# DIB_Power_Plane.net
KiCad netlist of a schematic drawn in Altium Designer
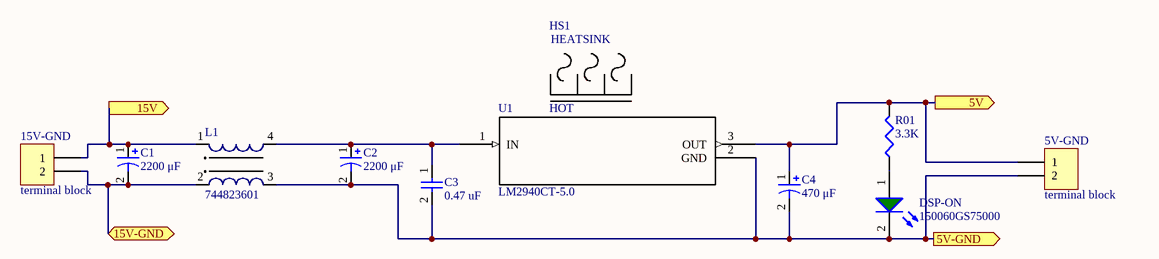
[diagram p0: DIB_Power_Plane.SchDoc]

(export (version "E")
  (design (tool "Eeschema 10.0.6"))
  (components
    (comp (ref "5V-GND")
      (value "terminal block")
      (footprint "691101710002")
      (description "WR-TBL Terminal block - serie 101-5.0mm")
      (fields
        (field (name "MANUFACTURER") "Würth Elektronik eiSos GmbH")
        (field (name "PARTNO") "691101710002")
        (field (name "CREATED BY") "Karrer Zheng")
      )
      (libsource (lib "Altium_TBL_5_00_101_HORIZONTAL_ENTRY_MODULAR_69110171000X_rev15e") (part "691101710002"))
    )
    (comp (ref "15V-GND")
      (value "terminal block")
      (footprint "691101710002")
      (description "WR-TBL Terminal block - serie 101-5.0mm")
      (fields
        (field (name "MANUFACTURER") "Würth Elektronik eiSos GmbH")
        (field (name "PARTNO") "691101710002")
        (field (name "CREATED BY") "Karrer Zheng")
      )
      (libsource (lib "") (part "691101710002_1"))
    )
    (comp (ref "C1")
      (value "2200 μF")
      (footprint "WCAP-ATG5 16x35.5x7.5x0.8")
      (description "WCAP-ATG5 Aluminum Electrolytic Capacitors , 2200 μF; + / - 20%; 50 V , 16 x 35,5")
      (fields
        (field (name "MANUFACTURER") "Wurth Elektronik")
        (field (name "PARTNO") "860020680030")
        (field (name "E-MAIL") "libraries@we-online.com")
        (field (name "CREATED BY") "Karrer Zheng")
      )
      (libsource (lib "WCAP-ATG5_rev15a") (part "WCAP-ATG5 16x35.5x7.5x0.8 860020680030"))
    )
    (comp (ref "C2")
      (value "2200 μF")
      (footprint "WCAP-ATG5 16x35.5x7.5x0.8")
      (description "WCAP-ATG5 Aluminum Electrolytic Capacitors , 2200 μF; + / - 20%; 50 V , 16 x 35,5")
      (fields
        (field (name "MANUFACTURER") "Wurth Elektronik")
        (field (name "PARTNO") "860020680030")
        (field (name "E-MAIL") "libraries@we-online.com")
        (field (name "CREATED BY") "Karrer Zheng")
      )
      (libsource (lib "WCAP-ATG5_rev15a") (part "WCAP-ATG5 16x35.5x7.5x0.8 860020680030"))
    )
    (comp (ref "C3")
      (value "0.47 uF")
      (footprint "WCAP-FTXX 7,5x10x12x6")
      (description "WCAP-FTXX Film Capacitors, C=68000 pF")
      (fields
        (field (name "MANUFACTURER") "Wurth Elektronik")
        (field (name "PARTNO") "890334022017")
        (field (name "E-MAIL") "libraries@we-online.com")
        (field (name "CREATED BY") "Karrer Zheng")
      )
      (libsource (lib "WCAP-FTXX_rev15a") (part "WCAP-FTXX 7,5x10x12x6 890334022017"))
    )
    (comp (ref "C4")
      (value "470 μF")
      (footprint "WCAP-ATG8 8x11.5x3.5x0.5")
      (description "WCAP-ATG8 Aluminum Electrolytic Capacitors , 470 μF; + / - 20%; 25 V , 8 x 11,5")
      (fields
        (field (name "MANUFACTURER") "Wurth Elektronik")
        (field (name "PARTNO") "860010474013")
        (field (name "E-MAIL") "libraries@we-online.com")
        (field (name "CREATED BY") "Karrer Zheng")
      )
      (libsource (lib "WCAP-ATG8_rev15a") (part "WCAP-ATG8 8x11.5x3.5x0.5 860010474013"))
    )
    (comp (ref "DSP-ON")
      (value "150060GS75000")
      (footprint "LED_0603_Green")
      (description "SMD mono-color Chip LED, WL-SMCW, Green")
      (fields
        (field (name "MANUFACTURER") "W黵th Elektronik eiSos GmbH")
        (field (name "CREATED BY") "Christin Otto")
      )
      (libsource (lib "WL-SMCW_rev15b") (part "WL-SMCW 0603  150060GS75000"))
    )
    (comp (ref "HS1")
      (value "HOT")
      (footprint "AAVID53002B02500G-custom")
      (description "TO 220 heat sink L=25mm; B=15mm; H= 30mm")
      (libsource (lib "sink block") (part "TO-220 Heat Sink"))
    )
    (comp (ref "L1")
      (value "744823601")
      (footprint "WE-CMB_M_744823601")
      (description "WE-CMB Common Mode Power Line Choke, L = 1.0mH")
      (fields (field (name "MANUFACTURER") "Wurth Elektronik") (field (name "CREATED BY") "Baojun Chen"))
      (libsource (lib "Altium_WE-CMB_rev16a") (part "WE-CMB M, 744823601"))
    )
    (comp (ref "R01")
      (value "3.3K")
      (footprint "J1-0603")
      (description "Resistor")
      (fields (field (name "PUBLISHER") "Altium Limited"))
      (libsource (lib "Miscellaneous Devices") (part "Res3"))
    )
    (comp (ref "U1")
      (value "LM2940CT-5.0")
      (footprint "to220-123-v")
      (description "Imported")
      (fields (field (name "PARTNUMBER") "LM2940CT-12"))
      (libsource (lib "2016-04-05_16-30-10") (part "LM2940C_NDE_3"))
    )
  )
  (nets
    (net (code "1") (name "/5V") (class "Default")
      (node (ref "5V-GND") (pin "1") (pinfunction "1_1") (pintype "passive"))
      (node (ref "C4") (pin "1") (pinfunction "1_1") (pintype "passive"))
      (node (ref "R01") (pin "2") (pinfunction "2_2") (pintype "passive"))
      (node (ref "U1") (pin "3") (pinfunction "OUT_3") (pintype "output"))
    )
    (net (code "2") (name "/5V-GND") (class "Default")
      (node (ref "5V-GND") (pin "2") (pinfunction "2_2") (pintype "passive"))
      (node (ref "C2") (pin "2") (pinfunction "2_2") (pintype "passive"))
      (node (ref "C3") (pin "2") (pintype "passive"))
      (node (ref "C4") (pin "2") (pinfunction "2_2") (pintype "passive"))
      (node (ref "DSP-ON") (pin "2") (pinfunction "C_2") (pintype "passive"))
      (node (ref "L1") (pin "3") (pinfunction "3_3") (pintype "passive"))
      (node (ref "U1") (pin "2") (pinfunction "GND_2") (pintype "passive"))
    )
    (net (code "3") (name "/15V") (class "Default")
      (node (ref "15V-GND") (pin "1") (pinfunction "1_1") (pintype "passive"))
      (node (ref "C1") (pin "1") (pinfunction "1_1") (pintype "passive"))
      (node (ref "L1") (pin "1") (pinfunction "1_1") (pintype "passive"))
    )
    (net (code "4") (name "/15V-GND") (class "Default")
      (node (ref "15V-GND") (pin "2") (pinfunction "2_2") (pintype "passive"))
      (node (ref "C1") (pin "2") (pinfunction "2_2") (pintype "passive"))
      (node (ref "L1") (pin "2") (pinfunction "2_2") (pintype "passive"))
    )
    (net (code "5") (name "Net-(DSP-ON-A)") (class "Default")
      (node (ref "DSP-ON") (pin "1") (pinfunction "A_1") (pintype "passive"))
      (node (ref "R01") (pin "1") (pinfunction "1_1") (pintype "passive"))
    )
    (net (code "6") (name "Net-(U1-IN)") (class "Default")
      (node (ref "C2") (pin "1") (pinfunction "1_1") (pintype "passive"))
      (node (ref "C3") (pin "1") (pintype "passive"))
      (node (ref "L1") (pin "4") (pinfunction "4_4") (pintype "passive"))
      (node (ref "U1") (pin "1") (pinfunction "IN_1") (pintype "input"))
    )
  )
)
